# Analog_Shared.net
KiCad netlist of a schematic drawn in Altium Designer
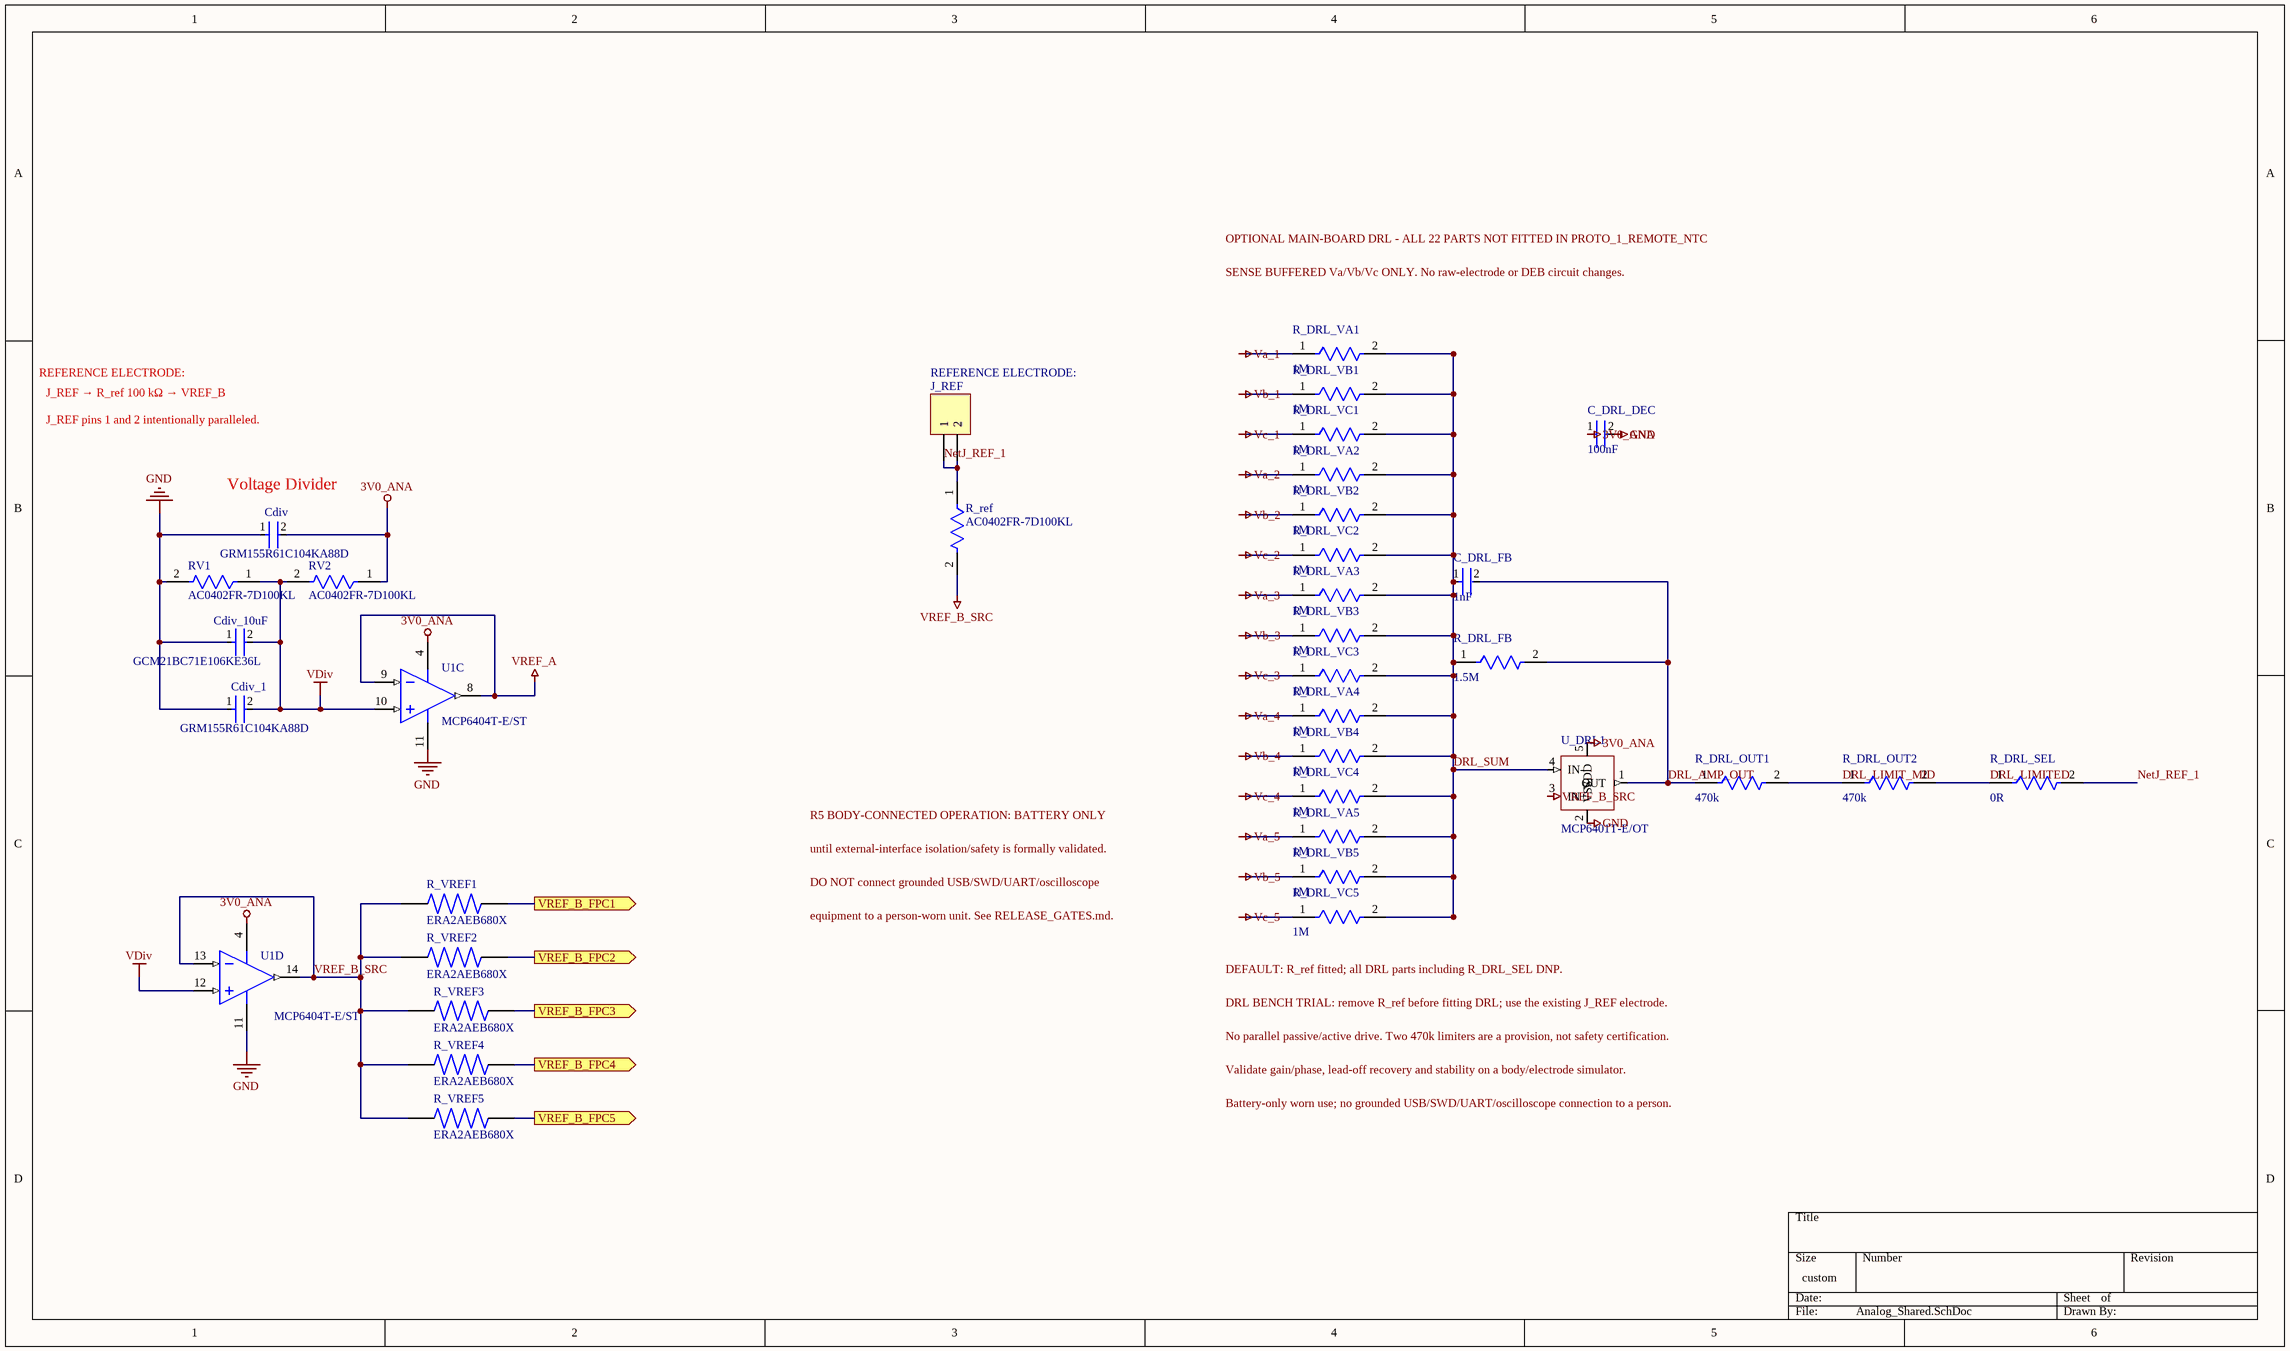
[diagram p0: Analog_Shared.SchDoc]

(export (version "E")
  (design (tool "Eeschema 10.0.6"))
  (components
    (comp (ref "Cdiv")
      (value "GRM155R61C104KA88D")
      (footprint "96DF66F8-B997-472F-A885-42BCAAE661B2_FP-GRM155-0_05-IPC_C:FP-GRM155-0_05-IPC_C")
      (description "CAP CER 0.1UF 16V X5R 0402")
      (fields (field (name "VOLTAGE") "16V") (field (name "TOLERANCE") "10%"))
      (libsource (lib "EMG_Controlled_R5") (part "EMG_R5_Cdiv"))
    )
    (comp (ref "Cdiv_1")
      (value "GRM155R61C104KA88D")
      (footprint "96DF66F8-B997-472F-A885-42BCAAE661B2_FP-GRM155-0_05-IPC_C:FP-GRM155-0_05-IPC_C")
      (description "CAP CER 0.1UF 16V X5R 0402")
      (fields (field (name "VOLTAGE") "16V") (field (name "TOLERANCE") "10%"))
      (libsource (lib "EMG_Controlled_R5") (part "EMG_R5_Cdiv_1"))
    )
    (comp (ref "Cdiv_10uF")
      (value "GCM21BC71E106KE36L")
      (footprint "936D640C-6583-4BC1-90EC-E059FB2B465D_FP-GCM21B-0_2-e0_2_0_7-MFG:FP-GCM21B-0_2-e0_2_0_7-MFG")
      (description "10 µF ±10% 25V Ceramic Capacitor X7S 0805 (2012 Metric)")
      (libsource (lib "EMG_Controlled_R5") (part "EMG_R5_Cdiv_10uF"))
    )
    (comp (ref "C_DRL_DEC")
      (value "100nF")
      (footprint "EMG_DRL_C_R4:EMG_DRL_C0402")
      (description "Optional DRL provision; not fitted in PROTO_1_REMOTE_NTC")
      (fields
        (field (name "MANUFACTURER") "Murata Manufacturing")
        (field (name "MANUFACTURER PART NUMBER") "GRM155R71C104KA88D")
      )
      (libsource (lib "EMG_DRL_Controlled") (part "EMG_DRL_C_DRL_DEC"))
    )
    (comp (ref "C_DRL_FB")
      (value "1nF")
      (footprint "EMG_DRL_C_R4:EMG_DRL_C0402")
      (description "Optional DRL provision; not fitted in PROTO_1_REMOTE_NTC")
      (fields
        (field (name "MANUFACTURER") "Murata Manufacturing")
        (field (name "MANUFACTURER PART NUMBER") "GRM1555C1H102JA01D")
      )
      (libsource (lib "EMG_DRL_Controlled") (part "EMG_DRL_C_DRL_FB"))
    )
    (comp (ref "J_REF")
      (value "REFERENCE ELECTRODE:")
      (footprint "Miscellaneous_Connectors_0:HDR1X2")
      (description "Header, 2-Pin")
      (fields (field (name "PUBLISHER") "Altium Limited"))
      (libsource (lib "EMG_Controlled_R5") (part "EMG_R5_J_REF"))
    )
    (comp (ref "RV1")
      (value "AC0402FR-7D100KL")
      (footprint "7D606042-220B-45EE-95DD-CA1A974E4C0D_FP-AC0402-MFG:FP-AC0402-MFG")
      (description "AC0402 100KΩ 0.0625W 1.00%")
      (fields
        (field (name "MANUFACTURER") "Yageo")
        (field (name "OCTOPART") "https://octopart.com/ac0402fr-7d100kl-yageo-91024821")
      )
      (libsource (lib "EMG_Controlled_R5") (part "EMG_R5_RV1"))
    )
    (comp (ref "RV2")
      (value "AC0402FR-7D100KL")
      (footprint "7D606042-220B-45EE-95DD-CA1A974E4C0D_FP-AC0402-MFG:FP-AC0402-MFG")
      (description "AC0402 100KΩ 0.0625W 1.00%")
      (fields
        (field (name "MANUFACTURER") "Yageo")
        (field (name "OCTOPART") "https://octopart.com/ac0402fr-7d100kl-yageo-91024821")
      )
      (libsource (lib "EMG_Controlled_R5") (part "EMG_R5_RV2"))
    )
    (comp (ref "R_DRL_FB")
      (value "1.5M")
      (footprint "EMG_DRL_R_R4:EMG_DRL_R0603")
      (description "Optional DRL provision; not fitted in PROTO_1_REMOTE_NTC")
      (fields (field (name "TOLERANCE") "1%") (field (name "MANUFACTURER") "YAGEO"))
      (libsource (lib "EMG_DRL_Controlled") (part "EMG_DRL_R_DRL_FB"))
    )
    (comp (ref "R_DRL_OUT1")
      (value "470k")
      (footprint "EMG_DRL_R_R4:EMG_DRL_R0603")
      (description "Optional DRL provision; not fitted in PROTO_1_REMOTE_NTC")
      (fields (field (name "TOLERANCE") "1%") (field (name "MANUFACTURER") "Panasonic Industry"))
      (libsource (lib "EMG_DRL_Controlled") (part "EMG_DRL_R_DRL_OUT1"))
    )
    (comp (ref "R_DRL_OUT2")
      (value "470k")
      (footprint "EMG_DRL_R_R4:EMG_DRL_R0603")
      (description "Optional DRL provision; not fitted in PROTO_1_REMOTE_NTC")
      (fields (field (name "TOLERANCE") "1%") (field (name "MANUFACTURER") "Panasonic Industry"))
      (libsource (lib "EMG_DRL_Controlled") (part "EMG_DRL_R_DRL_OUT2"))
    )
    (comp (ref "R_DRL_SEL")
      (value "0R")
      (footprint "EMG_DRL_R_R4:EMG_DRL_R0603")
      (description "Optional DRL provision; not fitted in PROTO_1_REMOTE_NTC")
      (fields
        (field (name "TOLERANCE") "Jumper: 50mOhm maximum")
        (field (name "MANUFACTURER") "Panasonic Industry")
      )
      (libsource (lib "EMG_DRL_Controlled") (part "EMG_DRL_R_DRL_SEL"))
    )
    (comp (ref "R_DRL_VA1")
      (value "1M")
      (footprint "EMG_DRL_R_R4:EMG_DRL_R0603")
      (description "Optional DRL provision; not fitted in PROTO_1_REMOTE_NTC")
      (fields (field (name "TOLERANCE") "1%") (field (name "MANUFACTURER") "Panasonic Industry"))
      (libsource (lib "EMG_DRL_Controlled") (part "EMG_DRL_R_DRL_VA1"))
    )
    (comp (ref "R_DRL_VA2")
      (value "1M")
      (footprint "EMG_DRL_R_R4:EMG_DRL_R0603")
      (description "Optional DRL provision; not fitted in PROTO_1_REMOTE_NTC")
      (fields (field (name "TOLERANCE") "1%") (field (name "MANUFACTURER") "Panasonic Industry"))
      (libsource (lib "EMG_DRL_Controlled") (part "EMG_DRL_R_DRL_VA2"))
    )
    (comp (ref "R_DRL_VA3")
      (value "1M")
      (footprint "EMG_DRL_R_R4:EMG_DRL_R0603")
      (description "Optional DRL provision; not fitted in PROTO_1_REMOTE_NTC")
      (fields (field (name "TOLERANCE") "1%") (field (name "MANUFACTURER") "Panasonic Industry"))
      (libsource (lib "EMG_DRL_Controlled") (part "EMG_DRL_R_DRL_VA3"))
    )
    (comp (ref "R_DRL_VA4")
      (value "1M")
      (footprint "EMG_DRL_R_R4:EMG_DRL_R0603")
      (description "Optional DRL provision; not fitted in PROTO_1_REMOTE_NTC")
      (fields (field (name "TOLERANCE") "1%") (field (name "MANUFACTURER") "Panasonic Industry"))
      (libsource (lib "EMG_DRL_Controlled") (part "EMG_DRL_R_DRL_VA4"))
    )
    (comp (ref "R_DRL_VA5")
      (value "1M")
      (footprint "EMG_DRL_R_R4:EMG_DRL_R0603")
      (description "Optional DRL provision; not fitted in PROTO_1_REMOTE_NTC")
      (fields (field (name "TOLERANCE") "1%") (field (name "MANUFACTURER") "Panasonic Industry"))
      (libsource (lib "EMG_DRL_Controlled") (part "EMG_DRL_R_DRL_VA5"))
    )
    (comp (ref "R_DRL_VB1")
      (value "1M")
      (footprint "EMG_DRL_R_R4:EMG_DRL_R0603")
      (description "Optional DRL provision; not fitted in PROTO_1_REMOTE_NTC")
      (fields (field (name "TOLERANCE") "1%") (field (name "MANUFACTURER") "Panasonic Industry"))
      (libsource (lib "EMG_DRL_Controlled") (part "EMG_DRL_R_DRL_VB1"))
    )
    (comp (ref "R_DRL_VB2")
      (value "1M")
      (footprint "EMG_DRL_R_R4:EMG_DRL_R0603")
      (description "Optional DRL provision; not fitted in PROTO_1_REMOTE_NTC")
      (fields (field (name "TOLERANCE") "1%") (field (name "MANUFACTURER") "Panasonic Industry"))
      (libsource (lib "EMG_DRL_Controlled") (part "EMG_DRL_R_DRL_VB2"))
    )
    (comp (ref "R_DRL_VB3")
      (value "1M")
      (footprint "EMG_DRL_R_R4:EMG_DRL_R0603")
      (description "Optional DRL provision; not fitted in PROTO_1_REMOTE_NTC")
      (fields (field (name "TOLERANCE") "1%") (field (name "MANUFACTURER") "Panasonic Industry"))
      (libsource (lib "EMG_DRL_Controlled") (part "EMG_DRL_R_DRL_VB3"))
    )
    (comp (ref "R_DRL_VB4")
      (value "1M")
      (footprint "EMG_DRL_R_R4:EMG_DRL_R0603")
      (description "Optional DRL provision; not fitted in PROTO_1_REMOTE_NTC")
      (fields (field (name "TOLERANCE") "1%") (field (name "MANUFACTURER") "Panasonic Industry"))
      (libsource (lib "EMG_DRL_Controlled") (part "EMG_DRL_R_DRL_VB4"))
    )
    (comp (ref "R_DRL_VB5")
      (value "1M")
      (footprint "EMG_DRL_R_R4:EMG_DRL_R0603")
      (description "Optional DRL provision; not fitted in PROTO_1_REMOTE_NTC")
      (fields (field (name "TOLERANCE") "1%") (field (name "MANUFACTURER") "Panasonic Industry"))
      (libsource (lib "EMG_DRL_Controlled") (part "EMG_DRL_R_DRL_VB5"))
    )
    (comp (ref "R_DRL_VC1")
      (value "1M")
      (footprint "EMG_DRL_R_R4:EMG_DRL_R0603")
      (description "Optional DRL provision; not fitted in PROTO_1_REMOTE_NTC")
      (fields (field (name "TOLERANCE") "1%") (field (name "MANUFACTURER") "Panasonic Industry"))
      (libsource (lib "EMG_DRL_Controlled") (part "EMG_DRL_R_DRL_VC1"))
    )
    (comp (ref "R_DRL_VC2")
      (value "1M")
      (footprint "EMG_DRL_R_R4:EMG_DRL_R0603")
      (description "Optional DRL provision; not fitted in PROTO_1_REMOTE_NTC")
      (fields (field (name "TOLERANCE") "1%") (field (name "MANUFACTURER") "Panasonic Industry"))
      (libsource (lib "EMG_DRL_Controlled") (part "EMG_DRL_R_DRL_VC2"))
    )
    (comp (ref "R_DRL_VC3")
      (value "1M")
      (footprint "EMG_DRL_R_R4:EMG_DRL_R0603")
      (description "Optional DRL provision; not fitted in PROTO_1_REMOTE_NTC")
      (fields (field (name "TOLERANCE") "1%") (field (name "MANUFACTURER") "Panasonic Industry"))
      (libsource (lib "EMG_DRL_Controlled") (part "EMG_DRL_R_DRL_VC3"))
    )
    (comp (ref "R_DRL_VC4")
      (value "1M")
      (footprint "EMG_DRL_R_R4:EMG_DRL_R0603")
      (description "Optional DRL provision; not fitted in PROTO_1_REMOTE_NTC")
      (fields (field (name "TOLERANCE") "1%") (field (name "MANUFACTURER") "Panasonic Industry"))
      (libsource (lib "EMG_DRL_Controlled") (part "EMG_DRL_R_DRL_VC4"))
    )
    (comp (ref "R_DRL_VC5")
      (value "1M")
      (footprint "EMG_DRL_R_R4:EMG_DRL_R0603")
      (description "Optional DRL provision; not fitted in PROTO_1_REMOTE_NTC")
      (fields (field (name "TOLERANCE") "1%") (field (name "MANUFACTURER") "Panasonic Industry"))
      (libsource (lib "EMG_DRL_Controlled") (part "EMG_DRL_R_DRL_VC5"))
    )
    (comp (ref "R_ref")
      (value "AC0402FR-7D100KL")
      (footprint "7D606042-220B-45EE-95DD-CA1A974E4C0D_FP-AC0402-MFG:FP-AC0402-MFG")
      (description "AC0402 100KΩ 0.0625W 1.00%")
      (fields
        (field (name "MANUFACTURER") "Yageo")
        (field (name "OCTOPART") "https://octopart.com/ac0402fr-7d100kl-yageo-91024821")
      )
      (libsource (lib "EMG_Controlled_R5") (part "EMG_R5_R_ref"))
    )
    (comp (ref "R_VREF1")
      (value "ERA2AEB680X")
      (footprint "ERA2AEB680X_0:RES_ERA2AEB680X")
      (libsource (lib "EMG_Controlled_R5") (part "EMG_R5_R_VREF1"))
    )
    (comp (ref "R_VREF2")
      (value "ERA2AEB680X")
      (footprint "ERA2AEB680X_0:RES_ERA2AEB680X")
      (libsource (lib "EMG_Controlled_R5") (part "EMG_R5_R_VREF2"))
    )
    (comp (ref "R_VREF3")
      (value "ERA2AEB680X")
      (footprint "ERA2AEB680X_0:RES_ERA2AEB680X")
      (libsource (lib "EMG_Controlled_R5") (part "EMG_R5_R_VREF3"))
    )
    (comp (ref "R_VREF4")
      (value "ERA2AEB680X")
      (footprint "ERA2AEB680X_0:RES_ERA2AEB680X")
      (libsource (lib "EMG_Controlled_R5") (part "EMG_R5_R_VREF4"))
    )
    (comp (ref "R_VREF5")
      (value "ERA2AEB680X")
      (footprint "ERA2AEB680X_0:RES_ERA2AEB680X")
      (libsource (lib "EMG_Controlled_R5") (part "EMG_R5_R_VREF5"))
    )
    (comp (ref "U1")
      (value "MCP6404T-E/ST")
      (footprint "CEF93338-31F0-4C64-85B6-F650E0BB75E3_TSSOP-ST14_N:TSSOP-ST14_N")
      (description "None")
      (libsource (lib "EMG_Controlled_R5") (part "EMG_R5_U1"))
    )
    (comp (ref "U_DRL1")
      (value "MCP6401T-E/OT")
      (footprint "EMG_DRL_U_R4:EMG_MCP6401_SOT23_5")
      (description "MCP6401 single operational amplifier, SOT-23-5; optional DRL, DNP")
      (fields (field (name "MANUFACTURER") "Microchip Technology"))
      (libsource (lib "EMG_DRL_Controlled") (part "EMG_MCP6401_SOT23_5_DRL"))
    )
  )
  (nets
    (net (code "1") (name "/DRL_AMP_OUT") (class "Default")
      (node (ref "C_DRL_FB") (pin "2") (pinfunction "2_2") (pintype "passive"))
      (node (ref "R_DRL_FB") (pin "2") (pinfunction "2_2") (pintype "passive"))
      (node (ref "R_DRL_OUT1") (pin "1") (pinfunction "1_1") (pintype "passive"))
      (node (ref "U_DRL1") (pin "1") (pinfunction "OUT_1") (pintype "output"))
    )
    (net (code "2") (name "/DRL_LIMITED") (class "Default")
      (node (ref "R_DRL_OUT2") (pin "2") (pinfunction "2_2") (pintype "passive"))
      (node (ref "R_DRL_SEL") (pin "1") (pinfunction "1_1") (pintype "passive"))
    )
    (net (code "3") (name "/DRL_LIMIT_MID") (class "Default")
      (node (ref "R_DRL_OUT1") (pin "2") (pinfunction "2_2") (pintype "passive"))
      (node (ref "R_DRL_OUT2") (pin "1") (pinfunction "1_1") (pintype "passive"))
    )
    (net (code "4") (name "/DRL_SUM") (class "Default")
      (node (ref "C_DRL_FB") (pin "1") (pinfunction "1_1") (pintype "passive"))
      (node (ref "R_DRL_FB") (pin "1") (pinfunction "1_1") (pintype "passive"))
      (node (ref "R_DRL_VA1") (pin "2") (pinfunction "2_2") (pintype "passive"))
      (node (ref "R_DRL_VA2") (pin "2") (pinfunction "2_2") (pintype "passive"))
      (node (ref "R_DRL_VA3") (pin "2") (pinfunction "2_2") (pintype "passive"))
      (node (ref "R_DRL_VA4") (pin "2") (pinfunction "2_2") (pintype "passive"))
      (node (ref "R_DRL_VA5") (pin "2") (pinfunction "2_2") (pintype "passive"))
      (node (ref "R_DRL_VB1") (pin "2") (pinfunction "2_2") (pintype "passive"))
      (node (ref "R_DRL_VB2") (pin "2") (pinfunction "2_2") (pintype "passive"))
      (node (ref "R_DRL_VB3") (pin "2") (pinfunction "2_2") (pintype "passive"))
      (node (ref "R_DRL_VB4") (pin "2") (pinfunction "2_2") (pintype "passive"))
      (node (ref "R_DRL_VB5") (pin "2") (pinfunction "2_2") (pintype "passive"))
      (node (ref "R_DRL_VC1") (pin "2") (pinfunction "2_2") (pintype "passive"))
      (node (ref "R_DRL_VC2") (pin "2") (pinfunction "2_2") (pintype "passive"))
      (node (ref "R_DRL_VC3") (pin "2") (pinfunction "2_2") (pintype "passive"))
      (node (ref "R_DRL_VC4") (pin "2") (pinfunction "2_2") (pintype "passive"))
      (node (ref "R_DRL_VC5") (pin "2") (pinfunction "2_2") (pintype "passive"))
      (node (ref "U_DRL1") (pin "4") (pinfunction "IN-_4") (pintype "input"))
    )
    (net (code "5") (name "/NetJ_REF_1") (class "Default")
      (node (ref "J_REF") (pin "1") (pinfunction "1_1") (pintype "passive"))
      (node (ref "J_REF") (pin "2") (pinfunction "2_2") (pintype "passive"))
      (node (ref "R_DRL_SEL") (pin "2") (pinfunction "2_2") (pintype "passive"))
      (node (ref "R_ref") (pin "1") (pinfunction "1_1") (pintype "passive"))
    )
    (net (code "6") (name "/VREF_B_FPC1") (class "Default")
      (node (ref "R_VREF1") (pin "2") (pinfunction "2_2") (pintype "passive"))
    )
    (net (code "7") (name "/VREF_B_FPC2") (class "Default")
      (node (ref "R_VREF2") (pin "2") (pinfunction "2_2") (pintype "passive"))
    )
    (net (code "8") (name "/VREF_B_FPC3") (class "Default")
      (node (ref "R_VREF3") (pin "2") (pinfunction "2_2") (pintype "passive"))
    )
    (net (code "9") (name "/VREF_B_FPC4") (class "Default")
      (node (ref "R_VREF4") (pin "2") (pinfunction "2_2") (pintype "passive"))
    )
    (net (code "10") (name "/VREF_B_FPC5") (class "Default")
      (node (ref "R_VREF5") (pin "2") (pinfunction "2_2") (pintype "passive"))
    )
    (net (code "11") (name "3V0_ANA") (class "Default")
      (node (ref "C_DRL_DEC") (pin "1") (pinfunction "1_1") (pintype "passive"))
      (node (ref "Cdiv") (pin "2") (pinfunction "2_2") (pintype "passive"))
      (node (ref "RV2") (pin "1") (pinfunction "1_1") (pintype "passive"))
      (node (ref "U1") (pin "4") (pinfunction "VDD_4") (pintype "power_in"))
      (node (ref "U_DRL1") (pin "5") (pinfunction "VDD_5") (pintype "power_in"))
    )
    (net (code "12") (name "GND") (class "Default")
      (node (ref "C_DRL_DEC") (pin "2") (pinfunction "2_2") (pintype "passive"))
      (node (ref "Cdiv") (pin "1") (pinfunction "1_1") (pintype "passive"))
      (node (ref "Cdiv_1") (pin "1") (pinfunction "1_1") (pintype "passive"))
      (node (ref "Cdiv_10uF") (pin "1") (pinfunction "1_1") (pintype "passive"))
      (node (ref "RV1") (pin "2") (pinfunction "2_2") (pintype "passive"))
      (node (ref "U1") (pin "11") (pinfunction "VSS_11") (pintype "power_in"))
      (node (ref "U_DRL1") (pin "2") (pinfunction "VSS_2") (pintype "power_in"))
    )
    (net (code "13") (name "VDiv") (class "Default")
      (node (ref "Cdiv_1") (pin "2") (pinfunction "2_2") (pintype "passive"))
      (node (ref "Cdiv_10uF") (pin "2") (pinfunction "2_2") (pintype "passive"))
      (node (ref "RV1") (pin "1") (pinfunction "1_1") (pintype "passive"))
      (node (ref "RV2") (pin "2") (pinfunction "2_2") (pintype "passive"))
      (node (ref "U1") (pin "10") (pinfunction "VINC+_10") (pintype "input"))
      (node (ref "U1") (pin "12") (pinfunction "VIND+_12") (pintype "input"))
    )
    (net (code "14") (name "VREF_A") (class "Default")
      (node (ref "U1") (pin "8") (pinfunction "VOUTC_8") (pintype "output"))
      (node (ref "U1") (pin "9") (pinfunction "VINC-_9") (pintype "input"))
    )
    (net (code "15") (name "VREF_B_SRC") (class "Default")
      (node (ref "R_VREF1") (pin "1") (pinfunction "1_1") (pintype "passive"))
      (node (ref "R_VREF2") (pin "1") (pinfunction "1_1") (pintype "passive"))
      (node (ref "R_VREF3") (pin "1") (pinfunction "1_1") (pintype "passive"))
      (node (ref "R_VREF4") (pin "1") (pinfunction "1_1") (pintype "passive"))
      (node (ref "R_VREF5") (pin "1") (pinfunction "1_1") (pintype "passive"))
      (node (ref "R_ref") (pin "2") (pinfunction "2_2") (pintype "passive"))
      (node (ref "U1") (pin "13") (pinfunction "VIND-_13") (pintype "input"))
      (node (ref "U1") (pin "14") (pinfunction "VOUTD_14") (pintype "output"))
      (node (ref "U_DRL1") (pin "3") (pinfunction "IN+_3") (pintype "input"))
    )
    (net (code "16") (name "Va_1") (class "Default")
      (node (ref "R_DRL_VA1") (pin "1") (pinfunction "1_1") (pintype "passive"))
    )
    (net (code "17") (name "Va_2") (class "Default")
      (node (ref "R_DRL_VA2") (pin "1") (pinfunction "1_1") (pintype "passive"))
    )
    (net (code "18") (name "Va_3") (class "Default")
      (node (ref "R_DRL_VA3") (pin "1") (pinfunction "1_1") (pintype "passive"))
    )
    (net (code "19") (name "Va_4") (class "Default")
      (node (ref "R_DRL_VA4") (pin "1") (pinfunction "1_1") (pintype "passive"))
    )
    (net (code "20") (name "Va_5") (class "Default")
      (node (ref "R_DRL_VA5") (pin "1") (pinfunction "1_1") (pintype "passive"))
    )
    (net (code "21") (name "Vb_1") (class "Default")
      (node (ref "R_DRL_VB1") (pin "1") (pinfunction "1_1") (pintype "passive"))
    )
    (net (code "22") (name "Vb_2") (class "Default")
      (node (ref "R_DRL_VB2") (pin "1") (pinfunction "1_1") (pintype "passive"))
    )
    (net (code "23") (name "Vb_3") (class "Default")
      (node (ref "R_DRL_VB3") (pin "1") (pinfunction "1_1") (pintype "passive"))
    )
    (net (code "24") (name "Vb_4") (class "Default")
      (node (ref "R_DRL_VB4") (pin "1") (pinfunction "1_1") (pintype "passive"))
    )
    (net (code "25") (name "Vb_5") (class "Default")
      (node (ref "R_DRL_VB5") (pin "1") (pinfunction "1_1") (pintype "passive"))
    )
    (net (code "26") (name "Vc_1") (class "Default")
      (node (ref "R_DRL_VC1") (pin "1") (pinfunction "1_1") (pintype "passive"))
    )
    (net (code "27") (name "Vc_2") (class "Default")
      (node (ref "R_DRL_VC2") (pin "1") (pinfunction "1_1") (pintype "passive"))
    )
    (net (code "28") (name "Vc_3") (class "Default")
      (node (ref "R_DRL_VC3") (pin "1") (pinfunction "1_1") (pintype "passive"))
    )
    (net (code "29") (name "Vc_4") (class "Default")
      (node (ref "R_DRL_VC4") (pin "1") (pinfunction "1_1") (pintype "passive"))
    )
    (net (code "30") (name "Vc_5") (class "Default")
      (node (ref "R_DRL_VC5") (pin "1") (pinfunction "1_1") (pintype "passive"))
    )
  )
)
